# microm_schem2.net
KiCad netlist of a schematic drawn in EAGLE
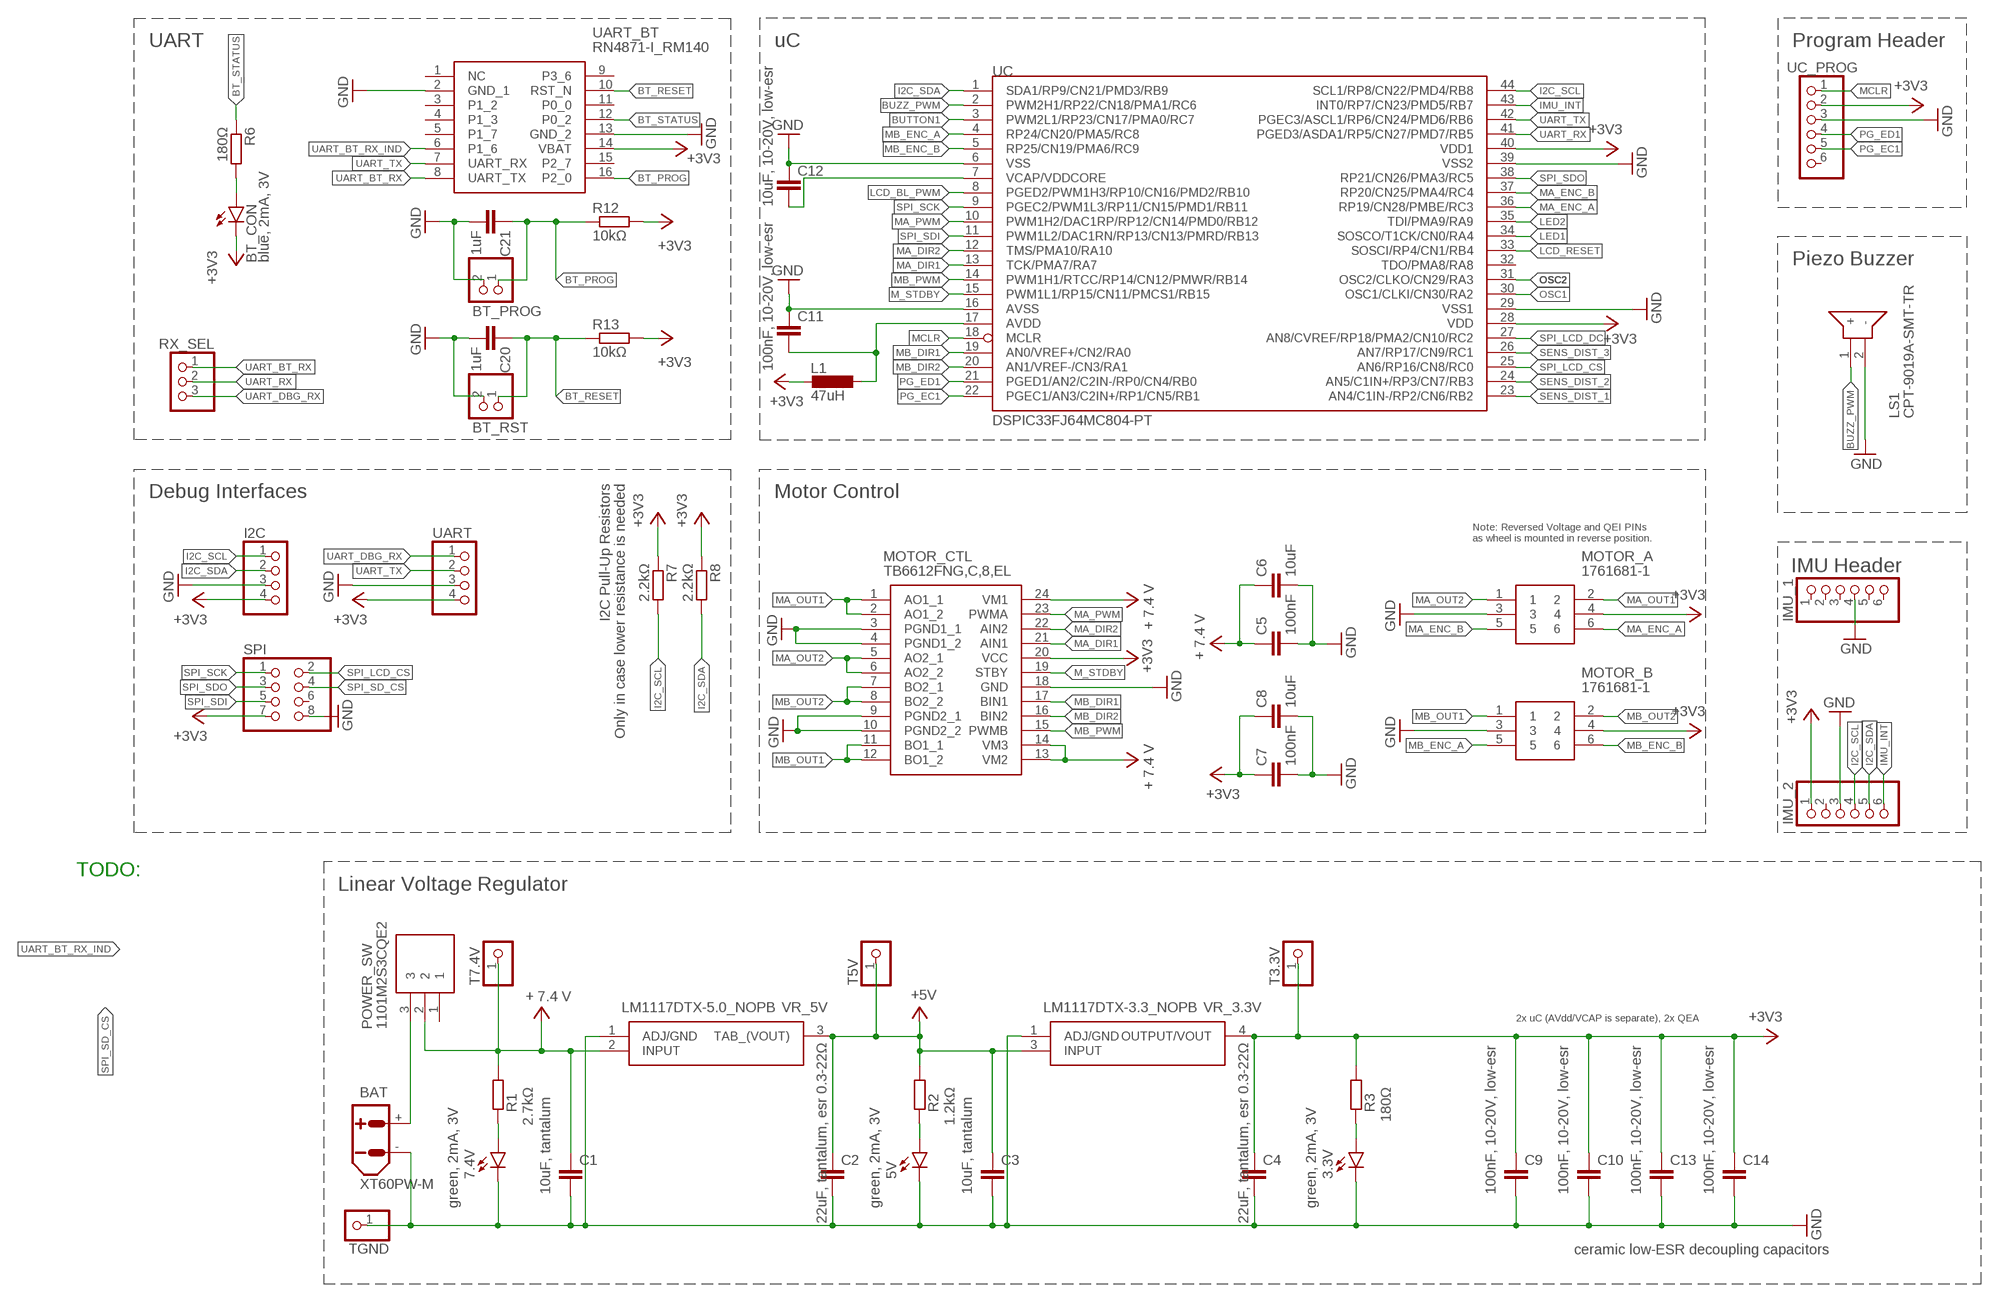
[diagram p0: schematic, sheet 1, part 1 of 2]
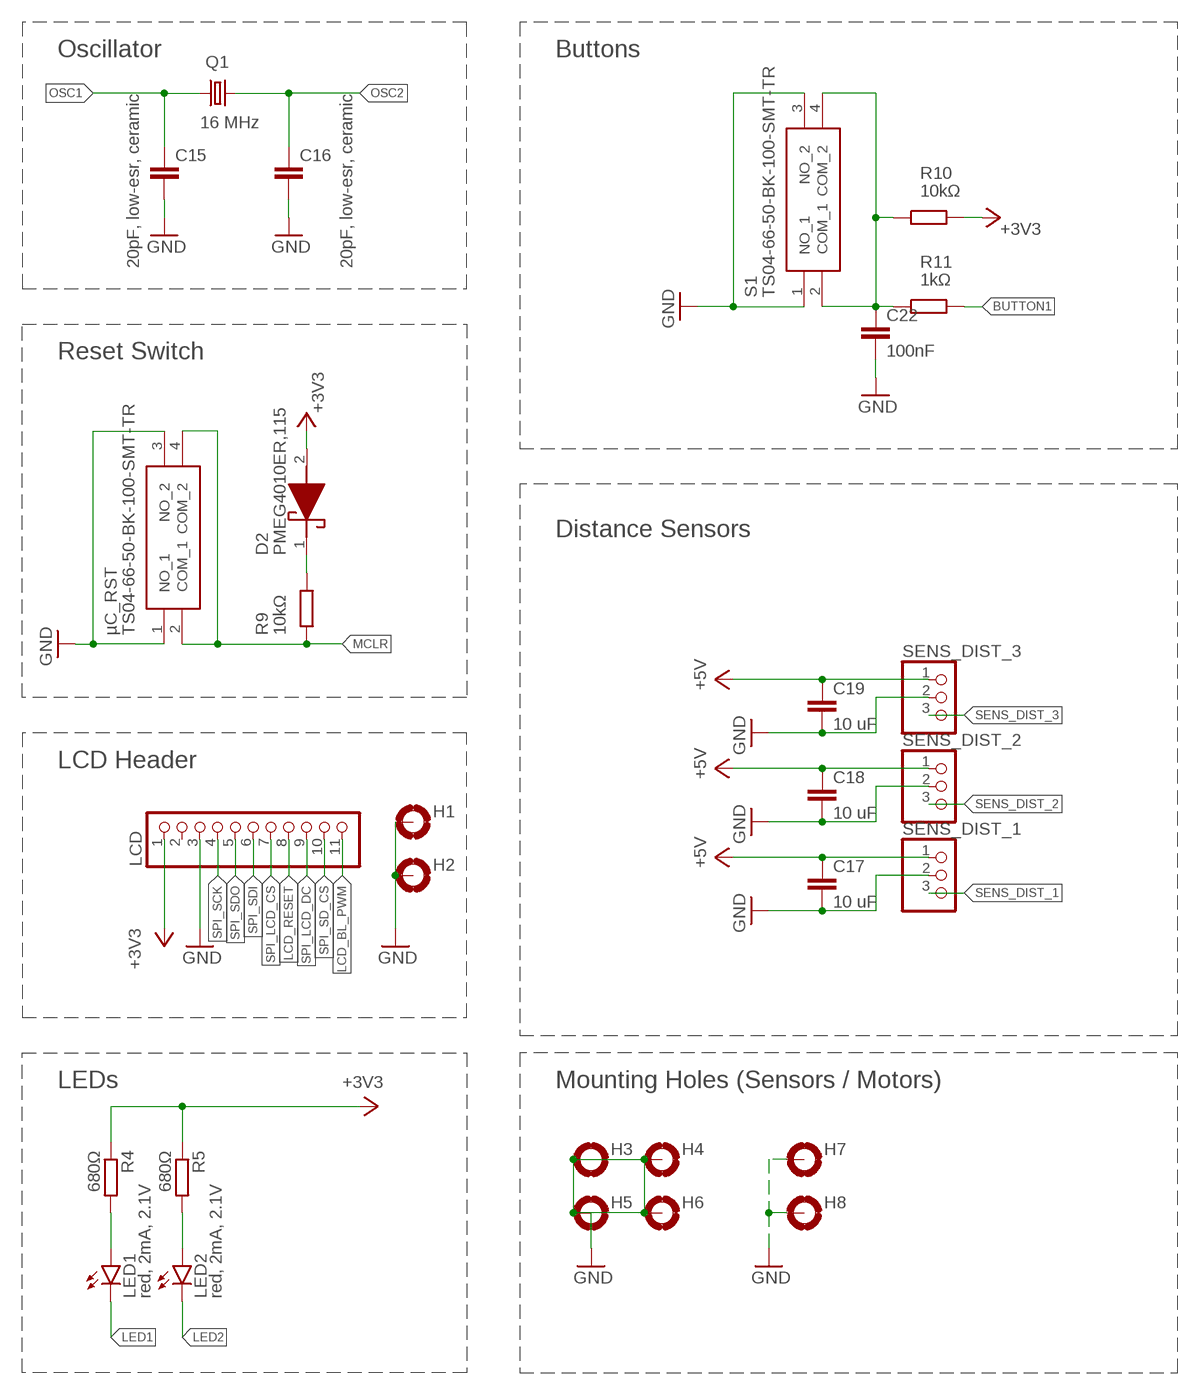
[diagram p1: schematic, sheet 1, part 2 of 2]

(export (version "E")
  (design (tool "Eeschema 10.0.6"))
  (components
    (comp (ref "3.3V")
      (value "green, 2mA, 3V")
      (footprint "eagle-import:CHIP-LED0805")
      (libsource (lib "eagle-import") (part "LEDCHIP-LED0805"))
    )
    (comp (ref "5V")
      (value "green, 2mA, 3V")
      (footprint "eagle-import:CHIP-LED0805")
      (libsource (lib "eagle-import") (part "LEDCHIP-LED0805"))
    )
    (comp (ref "7.4V")
      (value "green, 2mA, 3V")
      (footprint "eagle-import:CHIP-LED0805")
      (libsource (lib "eagle-import") (part "LEDCHIP-LED0805"))
    )
    (comp (ref "BAT")
      (value "XT60PW-M")
      (footprint "eagle-import:XT60PW-M")
      (libsource (lib "eagle-import") (part "XT60PW-M"))
    )
    (comp (ref "BT_CON")
      (value "blue, 2mA, 3V")
      (footprint "eagle-import:CHIP-LED0805")
      (libsource (lib "eagle-import") (part "LEDCHIP-LED0805"))
    )
    (comp (ref "BT_PROG")
      (value "PINHD-1X2")
      (footprint "eagle-import:1X02")
      (libsource (lib "eagle-import") (part "PINHD-1X2"))
    )
    (comp (ref "BT_RST")
      (value "PINHD-1X2")
      (footprint "eagle-import:1X02")
      (libsource (lib "eagle-import") (part "PINHD-1X2"))
    )
    (comp (ref "C1")
      (value "10uF, tantalum")
      (footprint "eagle-import:C0805")
      (libsource (lib "eagle-import") (part "C-EUC0805"))
    )
    (comp (ref "C2")
      (value "22uF, tantalum, esr 0.3-22Ω")
      (footprint "eagle-import:C0805")
      (libsource (lib "eagle-import") (part "C-EUC0805"))
    )
    (comp (ref "C3")
      (value "10uF, tantalum")
      (footprint "eagle-import:C0805")
      (libsource (lib "eagle-import") (part "C-EUC0805"))
    )
    (comp (ref "C4")
      (value "22uF, tantalum, esr 0.3-22Ω")
      (footprint "eagle-import:C0805")
      (libsource (lib "eagle-import") (part "C-EUC0805"))
    )
    (comp (ref "C5")
      (value "100nF")
      (footprint "eagle-import:C0805")
      (libsource (lib "eagle-import") (part "C-EUC0805"))
    )
    (comp (ref "C6")
      (value "10uF")
      (footprint "eagle-import:C0805")
      (libsource (lib "eagle-import") (part "C-EUC0805"))
    )
    (comp (ref "C7")
      (value "100nF")
      (footprint "eagle-import:C0805")
      (libsource (lib "eagle-import") (part "C-EUC0805"))
    )
    (comp (ref "C8")
      (value "10uF")
      (footprint "eagle-import:C0805")
      (libsource (lib "eagle-import") (part "C-EUC0805"))
    )
    (comp (ref "C9")
      (value "100nF, 10-20V, low-esr")
      (footprint "eagle-import:C0805")
      (libsource (lib "eagle-import") (part "C-EUC0805"))
    )
    (comp (ref "C10")
      (value "100nF, 10-20V, low-esr")
      (footprint "eagle-import:C0805")
      (libsource (lib "eagle-import") (part "C-EUC0805"))
    )
    (comp (ref "C11")
      (value "100nF, 10-20V, low-esr")
      (footprint "eagle-import:C0805")
      (libsource (lib "eagle-import") (part "C-EUC0805"))
    )
    (comp (ref "C12")
      (value "10uF, 10-20V, low-esr")
      (footprint "eagle-import:C0805")
      (libsource (lib "eagle-import") (part "C-EUC0805"))
    )
    (comp (ref "C13")
      (value "100nF, 10-20V, low-esr")
      (footprint "eagle-import:C0805")
      (libsource (lib "eagle-import") (part "C-EUC0805"))
    )
    (comp (ref "C14")
      (value "100nF, 10-20V, low-esr")
      (footprint "eagle-import:C0805")
      (libsource (lib "eagle-import") (part "C-EUC0805"))
    )
    (comp (ref "C15")
      (value "20pF, low-esr, ceramic")
      (footprint "eagle-import:C0805")
      (libsource (lib "eagle-import") (part "C-EUC0805"))
    )
    (comp (ref "C16")
      (value "20pF, low-esr, ceramic")
      (footprint "eagle-import:C0805")
      (libsource (lib "eagle-import") (part "C-EUC0805"))
    )
    (comp (ref "C17")
      (value "10 uF")
      (footprint "eagle-import:C0805")
      (libsource (lib "eagle-import") (part "C-EUC0805"))
    )
    (comp (ref "C18")
      (value "10 uF")
      (footprint "eagle-import:C0805")
      (libsource (lib "eagle-import") (part "C-EUC0805"))
    )
    (comp (ref "C19")
      (value "10 uF")
      (footprint "eagle-import:C0805")
      (libsource (lib "eagle-import") (part "C-EUC0805"))
    )
    (comp (ref "C20")
      (value "1uF")
      (footprint "eagle-import:C0805")
      (libsource (lib "eagle-import") (part "C-EUC0805"))
    )
    (comp (ref "C21")
      (value "1uF")
      (footprint "eagle-import:C0805")
      (libsource (lib "eagle-import") (part "C-EUC0805"))
    )
    (comp (ref "C22")
      (value "100nF")
      (footprint "eagle-import:C0805")
      (libsource (lib "eagle-import") (part "C-EUC0805"))
    )
    (comp (ref "D2")
      (value "PMEG4010ER,115")
      (footprint "eagle-import:PMEG4010ER115")
      (fields (field (name "MOUSER_PART_NUMBER") "771-PMEG4010ER115"))
      (libsource (lib "eagle-import") (part "PMEG4010ER,115"))
    )
    (comp (ref "H1")
      (value "MOUNT-PAD-ROUND2.8")
      (footprint "eagle-import:2,8-PAD")
      (libsource (lib "eagle-import") (part "MOUNT-PAD-ROUND2.8"))
    )
    (comp (ref "H2")
      (value "MOUNT-PAD-ROUND2.8")
      (footprint "eagle-import:2,8-PAD")
      (libsource (lib "eagle-import") (part "MOUNT-PAD-ROUND2.8"))
    )
    (comp (ref "H3")
      (value "MOUNT-PAD-ROUND2.8")
      (footprint "eagle-import:2,8-PAD")
      (libsource (lib "eagle-import") (part "holes_46782911_MOUNT-PAD-ROUND2.8"))
    )
    (comp (ref "H4")
      (value "MOUNT-PAD-ROUND2.8")
      (footprint "eagle-import:2,8-PAD")
      (libsource (lib "eagle-import") (part "holes_46782911_MOUNT-PAD-ROUND2.8"))
    )
    (comp (ref "H5")
      (value "MOUNT-PAD-ROUND2.8")
      (footprint "eagle-import:2,8-PAD")
      (libsource (lib "eagle-import") (part "holes_46782911_MOUNT-PAD-ROUND2.8"))
    )
    (comp (ref "H6")
      (value "MOUNT-PAD-ROUND2.8")
      (footprint "eagle-import:2,8-PAD")
      (libsource (lib "eagle-import") (part "holes_46782911_MOUNT-PAD-ROUND2.8"))
    )
    (comp (ref "H7")
      (value "MOUNT-PAD-ROUND2.8")
      (footprint "eagle-import:2,8-PAD")
      (libsource (lib "eagle-import") (part "holes_46782911_MOUNT-PAD-ROUND2.8"))
    )
    (comp (ref "H8")
      (value "MOUNT-PAD-ROUND2.8")
      (footprint "eagle-import:2,8-PAD")
      (libsource (lib "eagle-import") (part "holes_46782911_MOUNT-PAD-ROUND2.8"))
    )
    (comp (ref "I2C")
      (value "PINHD-1X4")
      (footprint "eagle-import:1X04")
      (libsource (lib "eagle-import") (part "PINHD-1X4"))
    )
    (comp (ref "IMU_1")
      (value "PINHD-1X6")
      (footprint "eagle-import:1X06")
      (libsource (lib "eagle-import") (part "PINHD-1X6"))
    )
    (comp (ref "IMU_2")
      (value "PINHD-1X6")
      (footprint "eagle-import:1X06")
      (libsource (lib "eagle-import") (part "PINHD-1X6"))
    )
    (comp (ref "L1")
      (value "47uH")
      (footprint "eagle-import:L1812")
      (libsource (lib "eagle-import") (part "L-EUL1812"))
    )
    (comp (ref "LCD")
      (value "PINHD-1X11")
      (footprint "eagle-import:1X11")
      (libsource (lib "eagle-import") (part "PINHD-1X11"))
    )
    (comp (ref "LED1")
      (value "red, 2mA, 2.1V")
      (footprint "eagle-import:CHIPLED_0805")
      (libsource (lib "eagle-import") (part "LEDCHIPLED_0805"))
    )
    (comp (ref "LED2")
      (value "red, 2mA, 2.1V")
      (footprint "eagle-import:CHIPLED_0805")
      (libsource (lib "eagle-import") (part "LEDCHIPLED_0805"))
    )
    (comp (ref "LS1")
      (value "CPT-9019A-SMT-TR")
      (footprint "eagle-import:CPT9019ASMTTR")
      (fields (field (name "MOUSER_PART_NUMBER") "179-CPT-9019A-SMT-TR"))
      (libsource (lib "eagle-import") (part "CPT-9019A-SMT-TR"))
    )
    (comp (ref "MOTOR_A")
      (value "1761681-1")
      (footprint "eagle-import:SHDR6W67P254_2X3_1524X916X922P")
      (fields (field (name "MOUSER_PART_NUMBER") "571-1761681-1"))
      (libsource (lib "eagle-import") (part "1761681-1"))
    )
    (comp (ref "MOTOR_B")
      (value "1761681-1")
      (footprint "eagle-import:SHDR6W67P254_2X3_1524X916X922P")
      (fields (field (name "MOUSER_PART_NUMBER") "571-1761681-1"))
      (libsource (lib "eagle-import") (part "1761681-1"))
    )
    (comp (ref "MOTOR_CTL")
      (value "TB6612FNG,C,8,EL")
      (footprint "eagle-import:SOP65P760X160-24N")
      (fields (field (name "MOUSER_PART_NUMBER") "757-TB6612FNGC8EL"))
      (libsource (lib "eagle-import") (part "TB6612FNG,C,8,EL"))
    )
    (comp (ref "POWER_SW")
      (value "1101M2S3CQE2")
      (footprint "eagle-import:1000-SERIES(SPDT)")
      (fields (field (name "MOUSER_PART_NUMBER") "611-1101M2S3CQE2"))
      (libsource (lib "eagle-import") (part "1101M2S3CQE2"))
    )
    (comp (ref "Q1")
      (value "16 MHz")
      (footprint "eagle-import:HC49_S")
      (libsource (lib "eagle-import") (part "CRYSTALHC49S"))
    )
    (comp (ref "R1")
      (value "2.7kΩ")
      (footprint "eagle-import:R0805")
      (libsource (lib "eagle-import") (part "R-EU_R0805"))
    )
    (comp (ref "R2")
      (value "1.2kΩ")
      (footprint "eagle-import:R0805")
      (libsource (lib "eagle-import") (part "R-EU_R0805"))
    )
    (comp (ref "R3")
      (value "180Ω")
      (footprint "eagle-import:R0805")
      (libsource (lib "eagle-import") (part "R-EU_R0805"))
    )
    (comp (ref "R4")
      (value "680Ω")
      (footprint "eagle-import:R0805")
      (libsource (lib "eagle-import") (part "R-EU_R0805"))
    )
    (comp (ref "R5")
      (value "680Ω")
      (footprint "eagle-import:R0805")
      (libsource (lib "eagle-import") (part "R-EU_R0805"))
    )
    (comp (ref "R6")
      (value "180Ω")
      (footprint "eagle-import:R0805")
      (libsource (lib "eagle-import") (part "R-EU_R0805"))
    )
    (comp (ref "R7")
      (value "2.2kΩ")
      (footprint "eagle-import:R0805")
      (libsource (lib "eagle-import") (part "R-EU_R0805"))
    )
    (comp (ref "R8")
      (value "2.2kΩ")
      (footprint "eagle-import:R0805")
      (libsource (lib "eagle-import") (part "R-EU_R0805"))
    )
    (comp (ref "R9")
      (value "10kΩ")
      (footprint "eagle-import:R0805")
      (libsource (lib "eagle-import") (part "R-EU_R0805"))
    )
    (comp (ref "R10")
      (value "10kΩ")
      (footprint "eagle-import:R0805")
      (libsource (lib "eagle-import") (part "R-EU_R0805"))
    )
    (comp (ref "R11")
      (value "1kΩ")
      (footprint "eagle-import:R0805")
      (libsource (lib "eagle-import") (part "R-EU_R0805"))
    )
    (comp (ref "R12")
      (value "10kΩ")
      (footprint "eagle-import:R0805")
      (libsource (lib "eagle-import") (part "R-EU_R0805"))
    )
    (comp (ref "R13")
      (value "10kΩ")
      (footprint "eagle-import:R0805")
      (libsource (lib "eagle-import") (part "R-EU_R0805"))
    )
    (comp (ref "RX_SEL")
      (value "PINHD-1X3")
      (footprint "eagle-import:1X03")
      (libsource (lib "eagle-import") (part "PINHD-1X3"))
    )
    (comp (ref "S1")
      (value "TS04-66-50-BK-100-SMT-TR")
      (footprint "eagle-import:TS046650BK100SMTTR")
      (fields
        (field (name "MANUFACTURER_PART_NUMBER") "TS04-66-95-BK-160-SMT-TR")
        (field (name "MOUSER_PART_NUMBER") "179-TS046695BK160SMR")
      )
      (libsource (lib "eagle-import") (part "TS04-66-50-BK-100-SMT-TR"))
    )
    (comp (ref "SENS_DIST_1")
      (value "PINHD-1X3")
      (footprint "eagle-import:1X03")
      (libsource (lib "eagle-import") (part "PINHD-1X3"))
    )
    (comp (ref "SENS_DIST_2")
      (value "PINHD-1X3")
      (footprint "eagle-import:1X03")
      (libsource (lib "eagle-import") (part "PINHD-1X3"))
    )
    (comp (ref "SENS_DIST_3")
      (value "PINHD-1X3")
      (footprint "eagle-import:1X03")
      (libsource (lib "eagle-import") (part "PINHD-1X3"))
    )
    (comp (ref "SPI")
      (value "PINHD-2X4")
      (footprint "eagle-import:2X04")
      (libsource (lib "eagle-import") (part "PINHD-2X4"))
    )
    (comp (ref "T3.3V")
      (value "PINHD-1X1")
      (footprint "eagle-import:1X01")
      (libsource (lib "eagle-import") (part "PINHD-1X1"))
    )
    (comp (ref "T5V")
      (value "PINHD-1X1")
      (footprint "eagle-import:1X01")
      (libsource (lib "eagle-import") (part "PINHD-1X1"))
    )
    (comp (ref "T7.4V")
      (value "PINHD-1X1")
      (footprint "eagle-import:1X01")
      (libsource (lib "eagle-import") (part "PINHD-1X1"))
    )
    (comp (ref "TGND")
      (value "PINHD-1X1")
      (footprint "eagle-import:1X01")
      (libsource (lib "eagle-import") (part "PINHD-1X1"))
    )
    (comp (ref "UART")
      (value "PINHD-1X4")
      (footprint "eagle-import:1X04")
      (libsource (lib "eagle-import") (part "PINHD-1X4"))
    )
    (comp (ref "UART_BT")
      (value "RN4871-I_RM140")
      (footprint "eagle-import:RN4871IRM140")
      (fields
        (field (name "ARROW_PART_NUMBER") "RN4871-I/RM140")
        (field (name "MOUSER_PART_NUMBER") "579-RN4871-I/RM140")
      )
      (libsource (lib "eagle-import") (part "RN4871-I_RM140"))
    )
    (comp (ref "UC")
      (value "DSPIC33FJ64MC804-PT")
      (footprint "eagle-import:TQFP44")
      (libsource (lib "eagle-import") (part "DSPIC33FJ64MC804-PT"))
    )
    (comp (ref "UC_PROG")
      (value "PINHD-1X6")
      (footprint "eagle-import:1X06")
      (libsource (lib "eagle-import") (part "PINHD-1X6"))
    )
    (comp (ref "VR_3.3V")
      (value "LM1117DTX-3.3_NOPB")
      (footprint "eagle-import:LM1117DTX33NOPB")
      (fields
        (field (name "ARROW_PART_NUMBER") "LM1117DTX-3.3/NOPB")
        (field (name "MOUSER_PART_NUMBER") "926-LM1117DTX3.3NOPB")
      )
      (libsource (lib "eagle-import") (part "LM1117DTX-3.3_NOPB"))
    )
    (comp (ref "VR_5V")
      (value "LM1117DTX-5.0_NOPB")
      (footprint "eagle-import:LM78M05CDT")
      (fields
        (field (name "ARROW_PART_NUMBER") "LM1117DTX-5.0/NOPB")
        (field (name "MOUSER_PART_NUMBER") "926-LM1117DTX50NOPB")
      )
      (libsource (lib "eagle-import") (part "LM1117DTX-5.0_NOPB"))
    )
    (comp (ref "µC_RST")
      (value "TS04-66-50-BK-100-SMT-TR")
      (footprint "eagle-import:TS046650BK100SMTTR")
      (fields
        (field (name "MANUFACTURER_PART_NUMBER") "TS04-66-95-BK-160-SMT-TR")
        (field (name "MOUSER_PART_NUMBER") "179-TS046695BK160SMR")
      )
      (libsource (lib "eagle-import") (part "TS04-66-50-BK-100-SMT-TR"))
    )
  )
  (nets
    (net (code "1") (name "+ 7.4 V") (class "Default")
      (node (ref "C1") (pin "1") (pinfunction "1_1") (pintype "passive"))
      (node (ref "C5") (pin "1") (pinfunction "1_1") (pintype "passive"))
      (node (ref "C6") (pin "1") (pinfunction "1_1") (pintype "passive"))
      (node (ref "MOTOR_CTL") (pin "13") (pinfunction "VM2_13") (pintype "bidirectional"))
      (node (ref "MOTOR_CTL") (pin "14") (pinfunction "VM3_14") (pintype "bidirectional"))
      (node (ref "MOTOR_CTL") (pin "24") (pinfunction "VM1_24") (pintype "bidirectional"))
      (node (ref "POWER_SW") (pin "2") (pinfunction "2_2") (pintype "bidirectional"))
      (node (ref "R1") (pin "1") (pinfunction "1_1") (pintype "passive"))
      (node (ref "T7.4V") (pin "1") (pinfunction "1_1") (pintype "passive"))
      (node (ref "VR_5V") (pin "2") (pinfunction "INPUT_2") (pintype "bidirectional"))
    )
    (net (code "2") (name "+3V3") (class "Default")
      (node (ref "BT_CON") (pin "C") (pinfunction "C_C") (pintype "passive"))
      (node (ref "C10") (pin "1") (pinfunction "1_1") (pintype "passive"))
      (node (ref "C13") (pin "1") (pinfunction "1_1") (pintype "passive"))
      (node (ref "C14") (pin "1") (pinfunction "1_1") (pintype "passive"))
      (node (ref "C4") (pin "1") (pinfunction "1_1") (pintype "passive"))
      (node (ref "C7") (pin "1") (pinfunction "1_1") (pintype "passive"))
      (node (ref "C8") (pin "1") (pinfunction "1_1") (pintype "passive"))
      (node (ref "C9") (pin "1") (pinfunction "1_1") (pintype "passive"))
      (node (ref "D2") (pin "2") (pinfunction "A_2") (pintype "bidirectional"))
      (node (ref "I2C") (pin "4") (pinfunction "4_4") (pintype "passive"))
      (node (ref "IMU_2") (pin "1") (pinfunction "1_1") (pintype "passive"))
      (node (ref "L1") (pin "2") (pinfunction "2_2") (pintype "passive"))
      (node (ref "LCD") (pin "1") (pinfunction "1_1") (pintype "passive"))
      (node (ref "MOTOR_A") (pin "4") (pinfunction "4_4") (pintype "bidirectional"))
      (node (ref "MOTOR_B") (pin "4") (pinfunction "4_4") (pintype "bidirectional"))
      (node (ref "MOTOR_CTL") (pin "20") (pinfunction "VCC_20") (pintype "bidirectional"))
      (node (ref "R10") (pin "2") (pinfunction "2_2") (pintype "passive"))
      (node (ref "R12") (pin "2") (pinfunction "2_2") (pintype "passive"))
      (node (ref "R13") (pin "2") (pinfunction "2_2") (pintype "passive"))
      (node (ref "R3") (pin "1") (pinfunction "1_1") (pintype "passive"))
      (node (ref "R4") (pin "1") (pinfunction "1_1") (pintype "passive"))
      (node (ref "R5") (pin "1") (pinfunction "1_1") (pintype "passive"))
      (node (ref "R7") (pin "1") (pinfunction "1_1") (pintype "passive"))
      (node (ref "R8") (pin "1") (pinfunction "1_1") (pintype "passive"))
      (node (ref "SPI") (pin "7") (pinfunction "7_7") (pintype "passive"))
      (node (ref "T3.3V") (pin "1") (pinfunction "1_1") (pintype "passive"))
      (node (ref "UART") (pin "4") (pinfunction "4_4") (pintype "passive"))
      (node (ref "UART_BT") (pin "14") (pinfunction "VBAT_14") (pintype "bidirectional"))
      (node (ref "UC") (pin "28") (pinfunction "VDD_28") (pintype "power_in"))
      (node (ref "UC") (pin "40") (pinfunction "VDD1_40") (pintype "power_in"))
      (node (ref "UC_PROG") (pin "2") (pinfunction "2_2") (pintype "passive"))
      (node (ref "VR_3.3V") (pin "4") (pinfunction "OUTPUT/VOUT_4") (pintype "bidirectional"))
    )
    (net (code "3") (name "+5V") (class "Default")
      (node (ref "C17") (pin "1") (pinfunction "1_1") (pintype "passive"))
      (node (ref "C18") (pin "1") (pinfunction "1_1") (pintype "passive"))
      (node (ref "C19") (pin "1") (pinfunction "1_1") (pintype "passive"))
      (node (ref "C2") (pin "1") (pinfunction "1_1") (pintype "passive"))
      (node (ref "C3") (pin "1") (pinfunction "1_1") (pintype "passive"))
      (node (ref "R2") (pin "1") (pinfunction "1_1") (pintype "passive"))
      (node (ref "SENS_DIST_1") (pin "1") (pinfunction "1_1") (pintype "passive"))
      (node (ref "SENS_DIST_2") (pin "1") (pinfunction "1_1") (pintype "passive"))
      (node (ref "SENS_DIST_3") (pin "1") (pinfunction "1_1") (pintype "passive"))
      (node (ref "T5V") (pin "1") (pinfunction "1_1") (pintype "passive"))
      (node (ref "VR_3.3V") (pin "3") (pinfunction "INPUT_3") (pintype "bidirectional"))
      (node (ref "VR_5V") (pin "3") (pinfunction "TAB_(VOUT)_3") (pintype "bidirectional"))
    )
    (net (code "4") (name "BT_PROG") (class "Default")
      (node (ref "BT_PROG") (pin "1") (pinfunction "1_1") (pintype "passive"))
      (node (ref "C21") (pin "1") (pinfunction "1_1") (pintype "passive"))
      (node (ref "R12") (pin "1") (pinfunction "1_1") (pintype "passive"))
      (node (ref "UART_BT") (pin "16") (pinfunction "P2_0_16") (pintype "bidirectional"))
    )
    (net (code "5") (name "BT_RESET") (class "Default")
      (node (ref "BT_RST") (pin "1") (pinfunction "1_1") (pintype "passive"))
      (node (ref "C20") (pin "1") (pinfunction "1_1") (pintype "passive"))
      (node (ref "R13") (pin "1") (pinfunction "1_1") (pintype "passive"))
      (node (ref "UART_BT") (pin "10") (pinfunction "RST_N_10") (pintype "bidirectional"))
    )
    (net (code "6") (name "BT_STATUS") (class "Default")
      (node (ref "R6") (pin "1") (pinfunction "1_1") (pintype "passive"))
      (node (ref "UART_BT") (pin "12") (pinfunction "P0_2_12") (pintype "bidirectional"))
    )
    (net (code "7") (name "BUTTON1") (class "Default")
      (node (ref "R11") (pin "2") (pinfunction "2_2") (pintype "passive"))
      (node (ref "UC") (pin "3") (pinfunction "PWM2L1/RP23/CN17/PMA0/RC7_3") (pintype "bidirectional"))
    )
    (net (code "8") (name "BUZZ_PWM") (class "Default")
      (node (ref "LS1") (pin "1") (pinfunction "+_1") (pintype "bidirectional"))
      (node (ref "UC") (pin "2") (pinfunction "PWM2H1/RP22/CN18/PMA1/RC6_2") (pintype "bidirectional"))
    )
    (net (code "9") (name "GND") (class "Default")
      (node (ref "3.3V") (pin "C") (pinfunction "C_C") (pintype "passive"))
      (node (ref "5V") (pin "C") (pinfunction "C_C") (pintype "passive"))
      (node (ref "7.4V") (pin "C") (pinfunction "C_C") (pintype "passive"))
      (node (ref "BAT") (pin "-") (pinfunction "-_-") (pintype "power_in"))
      (node (ref "BT_PROG") (pin "2") (pinfunction "2_2") (pintype "passive"))
      (node (ref "BT_RST") (pin "2") (pinfunction "2_2") (pintype "passive"))
      (node (ref "C1") (pin "2") (pinfunction "2_2") (pintype "passive"))
      (node (ref "C10") (pin "2") (pinfunction "2_2") (pintype "passive"))
      (node (ref "C11") (pin "1") (pinfunction "1_1") (pintype "passive"))
      (node (ref "C12") (pin "1") (pinfunction "1_1") (pintype "passive"))
      (node (ref "C13") (pin "2") (pinfunction "2_2") (pintype "passive"))
      (node (ref "C14") (pin "2") (pinfunction "2_2") (pintype "passive"))
      (node (ref "C15") (pin "2") (pinfunction "2_2") (pintype "passive"))
      (node (ref "C16") (pin "2") (pinfunction "2_2") (pintype "passive"))
      (node (ref "C17") (pin "2") (pinfunction "2_2") (pintype "passive"))
      (node (ref "C18") (pin "2") (pinfunction "2_2") (pintype "passive"))
      (node (ref "C19") (pin "2") (pinfunction "2_2") (pintype "passive"))
      (node (ref "C2") (pin "2") (pinfunction "2_2") (pintype "passive"))
      (node (ref "C20") (pin "2") (pinfunction "2_2") (pintype "passive"))
      (node (ref "C21") (pin "2") (pinfunction "2_2") (pintype "passive"))
      (node (ref "C22") (pin "2") (pinfunction "2_2") (pintype "passive"))
      (node (ref "C3") (pin "2") (pinfunction "2_2") (pintype "passive"))
      (node (ref "C4") (pin "2") (pinfunction "2_2") (pintype "passive"))
      (node (ref "C5") (pin "2") (pinfunction "2_2") (pintype "passive"))
      (node (ref "C6") (pin "2") (pinfunction "2_2") (pintype "passive"))
      (node (ref "C7") (pin "2") (pinfunction "2_2") (pintype "passive"))
      (node (ref "C8") (pin "2") (pinfunction "2_2") (pintype "passive"))
      (node (ref "C9") (pin "2") (pinfunction "2_2") (pintype "passive"))
      (node (ref "H1") (pin "B2,8") (pinfunction "MOUNT_B2,8") (pintype "passive"))
      (node (ref "H2") (pin "B2,8") (pinfunction "MOUNT_B2,8") (pintype "passive"))
      (node (ref "H3") (pin "B2,8") (pinfunction "MOUNT_B2,8") (pintype "passive"))
      (node (ref "H4") (pin "B2,8") (pinfunction "MOUNT_B2,8") (pintype "passive"))
      (node (ref "H5") (pin "B2,8") (pinfunction "MOUNT_B2,8") (pintype "passive"))
      (node (ref "H6") (pin "B2,8") (pinfunction "MOUNT_B2,8") (pintype "passive"))
      (node (ref "H7") (pin "B2,8") (pinfunction "MOUNT_B2,8") (pintype "passive"))
      (node (ref "H8") (pin "B2,8") (pinfunction "MOUNT_B2,8") (pintype "passive"))
      (node (ref "I2C") (pin "3") (pinfunction "3_3") (pintype "passive"))
      (node (ref "IMU_1") (pin "4") (pinfunction "4_4") (pintype "passive"))
      (node (ref "IMU_2") (pin "3") (pinfunction "3_3") (pintype "passive"))
      (node (ref "LCD") (pin "3") (pinfunction "3_3") (pintype "passive"))
      (node (ref "LS1") (pin "2") (pinfunction "-_2") (pintype "bidirectional"))
      (node (ref "MOTOR_A") (pin "3") (pinfunction "3_3") (pintype "bidirectional"))
      (node (ref "MOTOR_B") (pin "3") (pinfunction "3_3") (pintype "bidirectional"))
      (node (ref "MOTOR_CTL") (pin "10") (pinfunction "PGND2_2_10") (pintype "bidirectional"))
      (node (ref "MOTOR_CTL") (pin "18") (pinfunction "GND_18") (pintype "bidirectional"))
      (node (ref "MOTOR_CTL") (pin "3") (pinfunction "PGND1_1_3") (pintype "bidirectional"))
      (node (ref "MOTOR_CTL") (pin "4") (pinfunction "PGND1_2_4") (pintype "bidirectional"))
      (node (ref "MOTOR_CTL") (pin "9") (pinfunction "PGND2_1_9") (pintype "bidirectional"))
      (node (ref "S1") (pin "1") (pinfunction "NO_1_1") (pintype "bidirectional"))
      (node (ref "S1") (pin "3") (pinfunction "NO_2_3") (pintype "bidirectional"))
      (node (ref "SENS_DIST_1") (pin "2") (pinfunction "2_2") (pintype "passive"))
      (node (ref "SENS_DIST_2") (pin "2") (pinfunction "2_2") (pintype "passive"))
      (node (ref "SENS_DIST_3") (pin "2") (pinfunction "2_2") (pintype "passive"))
      (node (ref "SPI") (pin "8") (pinfunction "8_8") (pintype "passive"))
      (node (ref "TGND") (pin "1") (pinfunction "1_1") (pintype "passive"))
      (node (ref "UART") (pin "3") (pinfunction "3_3") (pintype "passive"))
      (node (ref "UART_BT") (pin "13") (pinfunction "GND_2_13") (pintype "bidirectional"))
      (node (ref "UART_BT") (pin "2") (pinfunction "GND_1_2") (pintype "bidirectional"))
      (node (ref "UC") (pin "16") (pinfunction "AVSS_16") (pintype "power_in"))
      (node (ref "UC") (pin "29") (pinfunction "VSS1_29") (pintype "power_in"))
      (node (ref "UC") (pin "39") (pinfunction "VSS2_39") (pintype "power_in"))
      (node (ref "UC") (pin "6") (pinfunction "VSS_6") (pintype "power_in"))
      (node (ref "UC_PROG") (pin "3") (pinfunction "3_3") (pintype "passive"))
      (node (ref "VR_3.3V") (pin "1") (pinfunction "ADJ/GND_1") (pintype "bidirectional"))
      (node (ref "VR_5V") (pin "1") (pinfunction "ADJ/GND_1") (pintype "bidirectional"))
      (node (ref "µC_RST") (pin "1") (pinfunction "NO_1_1") (pintype "bidirectional"))
      (node (ref "µC_RST") (pin "3") (pinfunction "NO_2_3") (pintype "bidirectional"))
    )
    (net (code "10") (name "I2C_SCL") (class "Default")
      (node (ref "I2C") (pin "1") (pinfunction "1_1") (pintype "passive"))
      (node (ref "IMU_2") (pin "4") (pinfunction "4_4") (pintype "passive"))
      (node (ref "R7") (pin "2") (pinfunction "2_2") (pintype "passive"))
      (node (ref "UC") (pin "44") (pinfunction "SCL1/RP8/CN22/PMD4/RB8_44") (pintype "bidirectional"))
    )
    (net (code "11") (name "I2C_SDA") (class "Default")
      (node (ref "I2C") (pin "2") (pinfunction "2_2") (pintype "passive"))
      (node (ref "IMU_2") (pin "5") (pinfunction "5_5") (pintype "passive"))
      (node (ref "R8") (pin "2") (pinfunction "2_2") (pintype "passive"))
      (node (ref "UC") (pin "1") (pinfunction "SDA1/RP9/CN21/PMD3/RB9_1") (pintype "bidirectional"))
    )
    (net (code "12") (name "IMU_INT") (class "Default")
      (node (ref "IMU_2") (pin "6") (pinfunction "6_6") (pintype "passive"))
      (node (ref "UC") (pin "43") (pinfunction "INT0/RP7/CN23/PMD5/RB7_43") (pintype "bidirectional"))
    )
    (net (code "13") (name "LCD_BL_PWM") (class "Default")
      (node (ref "LCD") (pin "11") (pinfunction "11_11") (pintype "passive"))
      (node (ref "UC") (pin "8") (pinfunction "PGED2/PWM1H3/RP10/CN16/PMD2/RB10_8") (pintype "bidirectional"))
    )
    (net (code "14") (name "LCD_RESET") (class "Default")
      (node (ref "LCD") (pin "8") (pinfunction "8_8") (pintype "passive"))
      (node (ref "UC") (pin "33") (pinfunction "SOSCI/RP4/CN1/RB4_33") (pintype "bidirectional"))
    )
    (net (code "15") (name "LED1") (class "Default")
      (node (ref "LED1") (pin "C") (pinfunction "C_C") (pintype "passive"))
      (node (ref "UC") (pin "34") (pinfunction "SOSCO/T1CK/CN0/RA4_34") (pintype "bidirectional"))
    )
    (net (code "16") (name "LED2") (class "Default")
      (node (ref "LED2") (pin "C") (pinfunction "C_C") (pintype "passive"))
      (node (ref "UC") (pin "35") (pinfunction "TDI/PMA9/RA9_35") (pintype "bidirectional"))
    )
    (net (code "17") (name "MA_DIR1") (class "Default")
      (node (ref "MOTOR_CTL") (pin "21") (pinfunction "AIN1_21") (pintype "bidirectional"))
      (node (ref "UC") (pin "13") (pinfunction "TCK/PMA7/RA7_13") (pintype "bidirectional"))
    )
    (net (code "18") (name "MA_DIR2") (class "Default")
      (node (ref "MOTOR_CTL") (pin "22") (pinfunction "AIN2_22") (pintype "bidirectional"))
      (node (ref "UC") (pin "12") (pinfunction "TMS/PMA10/RA10_12") (pintype "bidirectional"))
    )
    (net (code "19") (name "MA_ENC_A") (class "Default")
      (node (ref "MOTOR_A") (pin "6") (pinfunction "6_6") (pintype "bidirectional"))
      (node (ref "UC") (pin "36") (pinfunction "RP19/CN28/PMBE/RC3_36") (pintype "bidirectional"))
    )
    (net (code "20") (name "MA_ENC_B") (class "Default")
      (node (ref "MOTOR_A") (pin "5") (pinfunction "5_5") (pintype "bidirectional"))
      (node (ref "UC") (pin "37") (pinfunction "RP20/CN25/PMA4/RC4_37") (pintype "bidirectional"))
    )
    (net (code "21") (name "MA_OUT1") (class "Default")
      (node (ref "MOTOR_A") (pin "2") (pinfunction "2_2") (pintype "bidirectional"))
      (node (ref "MOTOR_CTL") (pin "1") (pinfunction "AO1_1_1") (pintype "bidirectional"))
      (node (ref "MOTOR_CTL") (pin "2") (pinfunction "AO1_2_2") (pintype "bidirectional"))
    )
    (net (code "22") (name "MA_OUT2") (class "Default")
      (node (ref "MOTOR_A") (pin "1") (pinfunction "1_1") (pintype "bidirectional"))
      (node (ref "MOTOR_CTL") (pin "5") (pinfunction "AO2_1_5") (pintype "bidirectional"))
      (node (ref "MOTOR_CTL") (pin "6") (pinfunction "AO2_2_6") (pintype "bidirectional"))
    )
    (net (code "23") (name "MA_PWM") (class "Default")
      (node (ref "MOTOR_CTL") (pin "23") (pinfunction "PWMA_23") (pintype "bidirectional"))
      (node (ref "UC") (pin "10") (pinfunction "PWM1H2/DAC1RP/RP12/CN14/PMD0/RB12_10") (pintype "bidirectional"))
    )
    (net (code "24") (name "MB_DIR1") (class "Default")
      (node (ref "MOTOR_CTL") (pin "17") (pinfunction "BIN1_17") (pintype "bidirectional"))
      (node (ref "UC") (pin "19") (pinfunction "AN0/VREF+/CN2/RA0_19") (pintype "bidirectional"))
    )
    (net (code "25") (name "MB_DIR2") (class "Default")
      (node (ref "MOTOR_CTL") (pin "16") (pinfunction "BIN2_16") (pintype "bidirectional"))
      (node (ref "UC") (pin "20") (pinfunction "AN1/VREF-/CN3/RA1_20") (pintype "bidirectional"))
    )
    (net (code "26") (name "MB_ENC_A") (class "Default")
      (node (ref "MOTOR_B") (pin "5") (pinfunction "5_5") (pintype "bidirectional"))
      (node (ref "UC") (pin "4") (pinfunction "RP24/CN20/PMA5/RC8_4") (pintype "bidirectional"))
    )
    (net (code "27") (name "MB_ENC_B") (class "Default")
      (node (ref "MOTOR_B") (pin "6") (pinfunction "6_6") (pintype "bidirectional"))
      (node (ref "UC") (pin "5") (pinfunction "RP25/CN19/PMA6/RC9_5") (pintype "bidirectional"))
    )
    (net (code "28") (name "MB_OUT1") (class "Default")
      (node (ref "MOTOR_B") (pin "1") (pinfunction "1_1") (pintype "bidirectional"))
      (node (ref "MOTOR_CTL") (pin "11") (pinfunction "BO1_1_11") (pintype "bidirectional"))
      (node (ref "MOTOR_CTL") (pin "12") (pinfunction "BO1_2_12") (pintype "bidirectional"))
    )
    (net (code "29") (name "MB_OUT2") (class "Default")
      (node (ref "MOTOR_B") (pin "2") (pinfunction "2_2") (pintype "bidirectional"))
      (node (ref "MOTOR_CTL") (pin "7") (pinfunction "BO2_1_7") (pintype "bidirectional"))
      (node (ref "MOTOR_CTL") (pin "8") (pinfunction "BO2_2_8") (pintype "bidirectional"))
    )
    (net (code "30") (name "MB_PWM") (class "Default")
      (node (ref "MOTOR_CTL") (pin "15") (pinfunction "PWMB_15") (pintype "bidirectional"))
      (node (ref "UC") (pin "14") (pinfunction "PWM1H1/RTCC/RP14/CN12/PMWR/RB14_14") (pintype "bidirectional"))
    )
    (net (code "31") (name "MCLR") (class "Default")
      (node (ref "R9") (pin "1") (pinfunction "1_1") (pintype "passive"))
      (node (ref "UC") (pin "18") (pinfunction "MCLR_18") (pintype "input"))
      (node (ref "UC_PROG") (pin "1") (pinfunction "1_1") (pintype "passive"))
      (node (ref "µC_RST") (pin "2") (pinfunction "COM_1_2") (pintype "bidirectional"))
      (node (ref "µC_RST") (pin "4") (pinfunction "COM_2_4") (pintype "bidirectional"))
    )
    (net (code "32") (name "M_STDBY") (class "Default")
      (node (ref "MOTOR_CTL") (pin "19") (pinfunction "STBY_19") (pintype "bidirectional"))
      (node (ref "UC") (pin "15") (pinfunction "PWM1L1/RP15/CN11/PMCS1/RB15_15") (pintype "bidirectional"))
    )
    (net (code "33") (name "Net-(3.3V-PadA)") (class "Default")
      (node (ref "3.3V") (pin "A") (pinfunction "A_A") (pintype "passive"))
      (node (ref "R3") (pin "2") (pinfunction "2_2") (pintype "passive"))
    )
    (net (code "34") (name "Net-(5V-PadA)") (class "Default")
      (node (ref "5V") (pin "A") (pinfunction "A_A") (pintype "passive"))
      (node (ref "R2") (pin "2") (pinfunction "2_2") (pintype "passive"))
    )
    (net (code "35") (name "Net-(7.4V-PadA)") (class "Default")
      (node (ref "7.4V") (pin "A") (pinfunction "A_A") (pintype "passive"))
      (node (ref "R1") (pin "2") (pinfunction "2_2") (pintype "passive"))
    )
    (net (code "36") (name "Net-(BAT-Pad+)") (class "Default")
      (node (ref "BAT") (pin "+") (pinfunction "+_+") (pintype "power_in"))
      (node (ref "POWER_SW") (pin "3") (pinfunction "3_3") (pintype "bidirectional"))
    )
    (net (code "37") (name "Net-(BT_CON-PadA)") (class "Default")
      (node (ref "BT_CON") (pin "A") (pinfunction "A_A") (pintype "passive"))
      (node (ref "R6") (pin "2") (pinfunction "2_2") (pintype "passive"))
    )
    (net (code "38") (name "Net-(D2-K)") (class "Default")
      (node (ref "D2") (pin "1") (pinfunction "K_1") (pintype "bidirectional"))
      (node (ref "R9") (pin "2") (pinfunction "2_2") (pintype "passive"))
    )
    (net (code "39") (name "Net-(LED1-PadA)") (class "Default")
      (node (ref "LED1") (pin "A") (pinfunction "A_A") (pintype "passive"))
      (node (ref "R4") (pin "2") (pinfunction "2_2") (pintype "passive"))
    )
    (net (code "40") (name "Net-(LED2-PadA)") (class "Default")
      (node (ref "LED2") (pin "A") (pinfunction "A_A") (pintype "passive"))
      (node (ref "R5") (pin "2") (pinfunction "2_2") (pintype "passive"))
    )
    (net (code "41") (name "Net-(S1-COM_1)") (class "Default")
      (node (ref "C22") (pin "1") (pinfunction "1_1") (pintype "passive"))
      (node (ref "R10") (pin "1") (pinfunction "1_1") (pintype "passive"))
      (node (ref "R11") (pin "1") (pinfunction "1_1") (pintype "passive"))
      (node (ref "S1") (pin "2") (pinfunction "COM_1_2") (pintype "bidirectional"))
      (node (ref "S1") (pin "4") (pinfunction "COM_2_4") (pintype "bidirectional"))
    )
    (net (code "42") (name "Net-(UC-AVDD)") (class "Default")
      (node (ref "C11") (pin "2") (pinfunction "2_2") (pintype "passive"))
      (node (ref "L1") (pin "1") (pinfunction "1_1") (pintype "passive"))
      (node (ref "UC") (pin "17") (pinfunction "AVDD_17") (pintype "power_in"))
    )
    (net (code "43") (name "Net-(UC-VCAP{slash}VDDCORE)") (class "Default")
      (node (ref "C12") (pin "2") (pinfunction "2_2") (pintype "passive"))
      (node (ref "UC") (pin "7") (pinfunction "VCAP/VDDCORE_7") (pintype "power_in"))
    )
    (net (code "44") (name "OSC1") (class "Default")
      (node (ref "C15") (pin "1") (pinfunction "1_1") (pintype "passive"))
      (node (ref "Q1") (pin "1") (pinfunction "1_1") (pintype "passive"))
      (node (ref "UC") (pin "30") (pinfunction "OSC1/CLKI/CN30/RA2_30") (pintype "bidirectional"))
    )
    (net (code "45") (name "OSC2") (class "Default")
      (node (ref "C16") (pin "1") (pinfunction "1_1") (pintype "passive"))
      (node (ref "Q1") (pin "2") (pinfunction "2_2") (pintype "passive"))
      (node (ref "UC") (pin "31") (pinfunction "OSC2/CLKO/CN29/RA3_31") (pintype "bidirectional"))
    )
    (net (code "46") (name "PG_EC1") (class "Default")
      (node (ref "UC") (pin "22") (pinfunction "PGEC1/AN3/C2IN+/RP1/CN5/RB1_22") (pintype "bidirectional"))
      (node (ref "UC_PROG") (pin "5") (pinfunction "5_5") (pintype "passive"))
    )
    (net (code "47") (name "PG_ED1") (class "Default")
      (node (ref "UC") (pin "21") (pinfunction "PGED1/AN2/C2IN-/RP0/CN4/RB0_21") (pintype "bidirectional"))
      (node (ref "UC_PROG") (pin "4") (pinfunction "4_4") (pintype "passive"))
    )
    (net (code "48") (name "SENS_DIST_1") (class "Default")
      (node (ref "SENS_DIST_1") (pin "3") (pinfunction "3_3") (pintype "passive"))
      (node (ref "UC") (pin "23") (pinfunction "AN4/C1IN-/RP2/CN6/RB2_23") (pintype "bidirectional"))
    )
    (net (code "49") (name "SENS_DIST_2") (class "Default")
      (node (ref "SENS_DIST_2") (pin "3") (pinfunction "3_3") (pintype "passive"))
      (node (ref "UC") (pin "24") (pinfunction "AN5/C1IN+/RP3/CN7/RB3_24") (pintype "bidirectional"))
    )
    (net (code "50") (name "SENS_DIST_3") (class "Default")
      (node (ref "SENS_DIST_3") (pin "3") (pinfunction "3_3") (pintype "passive"))
      (node (ref "UC") (pin "26") (pinfunction "AN7/RP17/CN9/RC1_26") (pintype "bidirectional"))
    )
    (net (code "51") (name "SPI_LCD_CS") (class "Default")
      (node (ref "LCD") (pin "7") (pinfunction "7_7") (pintype "passive"))
      (node (ref "SPI") (pin "2") (pinfunction "2_2") (pintype "passive"))
      (node (ref "UC") (pin "25") (pinfunction "AN6/RP16/CN8/RC0_25") (pintype "bidirectional"))
    )
    (net (code "52") (name "SPI_LCD_DC") (class "Default")
      (node (ref "LCD") (pin "9") (pinfunction "9_9") (pintype "passive"))
      (node (ref "UC") (pin "27") (pinfunction "AN8/CVREF/RP18/PMA2/CN10/RC2_27") (pintype "bidirectional"))
    )
    (net (code "53") (name "SPI_SCK") (class "Default")
      (node (ref "LCD") (pin "4") (pinfunction "4_4") (pintype "passive"))
      (node (ref "SPI") (pin "1") (pinfunction "1_1") (pintype "passive"))
      (node (ref "UC") (pin "9") (pinfunction "PGEC2/PWM1L3/RP11/CN15/PMD1/RB11_9") (pintype "bidirectional"))
    )
    (net (code "54") (name "SPI_SDI") (class "Default")
      (node (ref "LCD") (pin "6") (pinfunction "6_6") (pintype "passive"))
      (node (ref "SPI") (pin "5") (pinfunction "5_5") (pintype "passive"))
      (node (ref "UC") (pin "11") (pinfunction "PWM1L2/DAC1RN/RP13/CN13/PMRD/RB13_11") (pintype "bidirectional"))
    )
    (net (code "55") (name "SPI_SDO") (class "Default")
      (node (ref "LCD") (pin "5") (pinfunction "5_5") (pintype "passive"))
      (node (ref "SPI") (pin "3") (pinfunction "3_3") (pintype "passive"))
      (node (ref "UC") (pin "38") (pinfunction "RP21/CN26/PMA3/RC5_38") (pintype "bidirectional"))
    )
    (net (code "56") (name "SPI_SD_CS") (class "Default")
      (node (ref "LCD") (pin "10") (pinfunction "10_10") (pintype "passive"))
      (node (ref "SPI") (pin "4") (pinfunction "4_4") (pintype "passive"))
    )
    (net (code "57") (name "UART_BT_RX") (class "Default")
      (node (ref "RX_SEL") (pin "1") (pinfunction "1_1") (pintype "passive"))
      (node (ref "UART_BT") (pin "8") (pinfunction "UART_TX_8") (pintype "bidirectional"))
    )
    (net (code "58") (name "UART_BT_RX_IND") (class "Default")
      (node (ref "UART_BT") (pin "6") (pinfunction "P1_6_6") (pintype "bidirectional"))
    )
    (net (code "59") (name "UART_DBG_RX") (class "Default")
      (node (ref "RX_SEL") (pin "3") (pinfunction "3_3") (pintype "passive"))
      (node (ref "UART") (pin "1") (pinfunction "1_1") (pintype "passive"))
    )
    (net (code "60") (name "UART_RX") (class "Default")
      (node (ref "RX_SEL") (pin "2") (pinfunction "2_2") (pintype "passive"))
      (node (ref "UC") (pin "41") (pinfunction "PGED3/ASDA1/RP5/CN27/PMD7/RB5_41") (pintype "bidirectional"))
    )
    (net (code "61") (name "UART_TX") (class "Default")
      (node (ref "UART") (pin "2") (pinfunction "2_2") (pintype "passive"))
      (node (ref "UART_BT") (pin "7") (pinfunction "UART_RX_7") (pintype "bidirectional"))
      (node (ref "UC") (pin "42") (pinfunction "PGEC3/ASCL1/RP6/CN24/PMD6/RB6_42") (pintype "bidirectional"))
    )
    (net (code "62") (name "unconnected-(IMU_1-Pad1)") (class "Default")
      (node (ref "IMU_1") (pin "1") (pinfunction "1_1") (pintype "passive"))
    )
    (net (code "63") (name "unconnected-(IMU_1-Pad2)") (class "Default")
      (node (ref "IMU_1") (pin "2") (pinfunction "2_2") (pintype "passive"))
    )
    (net (code "64") (name "unconnected-(IMU_1-Pad3)") (class "Default")
      (node (ref "IMU_1") (pin "3") (pinfunction "3_3") (pintype "passive"))
    )
    (net (code "65") (name "unconnected-(IMU_1-Pad5)") (class "Default")
      (node (ref "IMU_1") (pin "5") (pinfunction "5_5") (pintype "passive"))
    )
    (net (code "66") (name "unconnected-(IMU_1-Pad6)") (class "Default")
      (node (ref "IMU_1") (pin "6") (pinfunction "6_6") (pintype "passive"))
    )
    (net (code "67") (name "unconnected-(IMU_2-Pad2)") (class "Default")
      (node (ref "IMU_2") (pin "2") (pinfunction "2_2") (pintype "passive"))
    )
    (net (code "68") (name "unconnected-(LCD-Pad2)") (class "Default")
      (node (ref "LCD") (pin "2") (pinfunction "2_2") (pintype "passive"))
    )
    (net (code "69") (name "unconnected-(POWER_SW-Pad1)") (class "Default")
      (node (ref "POWER_SW") (pin "1") (pinfunction "1_1") (pintype "bidirectional"))
    )
    (net (code "70") (name "unconnected-(SPI-Pad6)") (class "Default")
      (node (ref "SPI") (pin "6") (pinfunction "6_6") (pintype "passive"))
    )
    (net (code "71") (name "unconnected-(UART_BT-NC-Pad1)") (class "Default")
      (node (ref "UART_BT") (pin "1") (pinfunction "NC_1") (pintype "no_connect"))
    )
    (net (code "72") (name "unconnected-(UART_BT-P0_0-Pad11)") (class "Default")
      (node (ref "UART_BT") (pin "11") (pinfunction "P0_0_11") (pintype "bidirectional"))
    )
    (net (code "73") (name "unconnected-(UART_BT-P1_2-Pad3)") (class "Default")
      (node (ref "UART_BT") (pin "3") (pinfunction "P1_2_3") (pintype "bidirectional"))
    )
    (net (code "74") (name "unconnected-(UART_BT-P1_3-Pad4)") (class "Default")
      (node (ref "UART_BT") (pin "4") (pinfunction "P1_3_4") (pintype "bidirectional"))
    )
    (net (code "75") (name "unconnected-(UART_BT-P1_7-Pad5)") (class "Default")
      (node (ref "UART_BT") (pin "5") (pinfunction "P1_7_5") (pintype "bidirectional"))
    )
    (net (code "76") (name "unconnected-(UART_BT-P2_7-Pad15)") (class "Default")
      (node (ref "UART_BT") (pin "15") (pinfunction "P2_7_15") (pintype "bidirectional"))
    )
    (net (code "77") (name "unconnected-(UART_BT-P3_6-Pad9)") (class "Default")
      (node (ref "UART_BT") (pin "9") (pinfunction "P3_6_9") (pintype "bidirectional"))
    )
    (net (code "78") (name "unconnected-(UC-TDO{slash}PMA8{slash}RA8-Pad32)") (class "Default")
      (node (ref "UC") (pin "32") (pinfunction "TDO/PMA8/RA8_32") (pintype "bidirectional"))
    )
    (net (code "79") (name "unconnected-(UC_PROG-Pad6)") (class "Default")
      (node (ref "UC_PROG") (pin "6") (pinfunction "6_6") (pintype "passive"))
    )
  )
)
